# StandaloneLeakDetector.net
KiCad netlist of a schematic drawn in Altium Designer
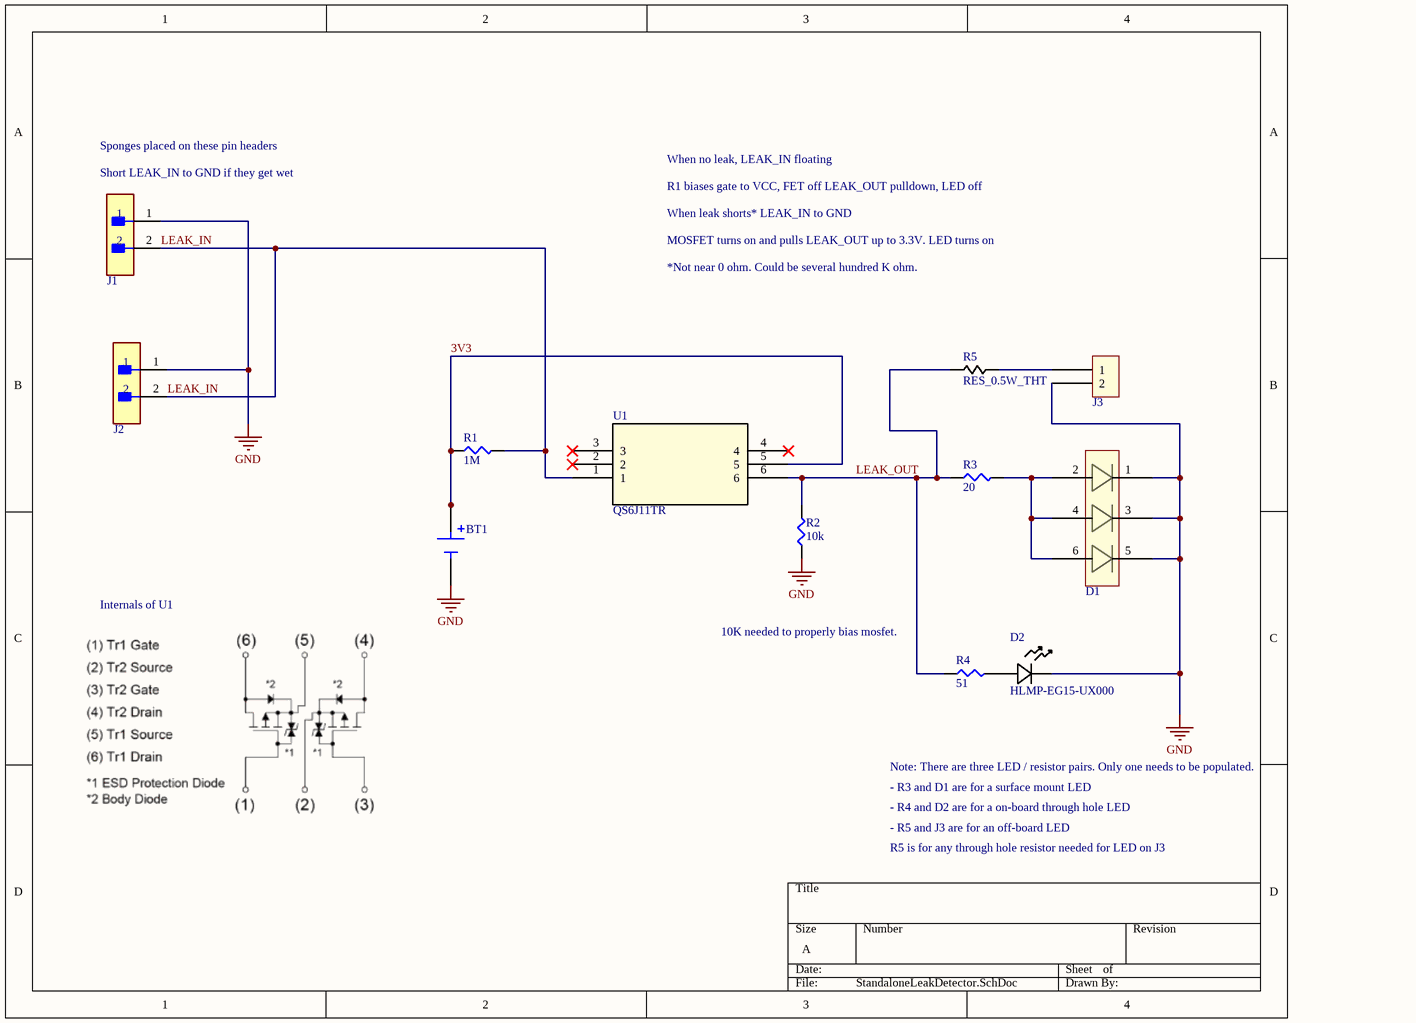
[diagram p0: StandaloneLeakDetector.SchDoc]

(export (version "E")
  (design (tool "Eeschema 10.0.6"))
  (components
    (comp (ref "BT1")
      (value "BAT-HLD-005-THM")
      (footprint "BAT_BAT-HLD-005-THM")
      (description "Battery Retainer Coin, 20.0mm 1 Cell PC Pin")
      (fields (field (name "MF") "Linx Technologies Inc."))
      (libsource (lib "URC_Lib") (part "BAT-HLD-005-THM"))
    )
    (comp (ref "D1") (value "SMTL6-RC") (footprint "SMTL6-RC") (libsource (lib "URC_Lib") (part "SMTL6-RC")))
    (comp (ref "D2")
      (value "HLMP-EG15-UX000")
      (footprint "LED_AVAGO_HLMP_XX15_AVA")
      (description "No Description Available")
      (fields (field (name "COPYRIGHT") "Copyright (C) 2022 Ultra Librarian. All rights reserved."))
      (libsource (lib "URC_Lib") (part "HLMP-EG15-UX000"))
    )
    (comp (ref "J1")
      (value "TSW-102-07-L-S")
      (footprint "FP-TSW-102-07-L-S-MFG")
      (description "CONN HEADER VERT 2POS 2.54MM")
      (libsource (lib "Altium Content Vault") (part "3bc925449376181038e59eaffc5286c"))
    )
    (comp (ref "J2")
      (value "TSW-102-07-L-S")
      (footprint "FP-TSW-102-07-L-S-MFG")
      (description "CONN HEADER VERT 2POS 2.54MM")
      (libsource (lib "Altium Content Vault") (part "3bc925449376181038e59eaffc5286c"))
    )
    (comp (ref "J3")
      (value "Header")
      (footprint "1x2 Header")
      (description "CONN HEADER VERT 2POS 2.54MM")
      (libsource (lib "URC_Lib") (part "1x2 Header"))
    )
    (comp (ref "R1")
      (value "1M")
      (footprint "SMD-0805-RES")
      (description "RES SMD 1M OHM 1% 1/8W 0805")
      (fields
        (field (name "PART NUMBER") "ERJ-6ENF1004V")
        (field (name "DIGI-KEY PART NUMBER") "P1.00MCCT-ND")
      )
      (libsource (lib "Panasonic_resistor_0805") (part "ERJ-6ENF1004V"))
    )
    (comp (ref "R2")
      (value "10k")
      (footprint "SMD-0805-RES")
      (description "RES SMD 10K OHM 1% 1/8W 0805")
      (fields
        (field (name "PART NUMBER") "ERJ-6ENF1002V")
        (field (name "DIGI-KEY PART NUMBER") "P10.0KCCT-ND")
      )
      (libsource (lib "Panasonic_resistor_0805") (part "ERJ-6ENF1002V"))
    )
    (comp (ref "R3")
      (value "20")
      (footprint "SMD-0805-RES")
      (description "RES SMD 20 OHM 1% 1/8W 0805")
      (fields
        (field (name "PART NUMBER") "ERJ-6ENF20R0V")
        (field (name "DIGI-KEY PART NUMBER") "P20.0CCT-ND")
      )
      (libsource (lib "Panasonic_resistor_0805") (part "ERJ-6ENF20R0V"))
    )
    (comp (ref "R4")
      (value "51")
      (footprint "SMD-0805-RES")
      (description "RES SMD 51 OHM 5% 1/8W 0805")
      (fields (field (name "PART NUMBER") "ERJ-6GEYJ510V") (field (name "DIGI-KEY PART NUMBER") "P51ACT-ND"))
      (libsource (lib "Panasonic_resistor_0805") (part "ERJ-6GEYJ510V"))
    )
    (comp (ref "R5")
      (value "RES_0.5W_THT")
      (footprint "RES_0.5W_THT")
      (description "Generic 0.5W through hole resistor")
      (libsource (lib "URC_Lib") (part "RES_0.5W_THT"))
    )
    (comp (ref "U1")
      (value "QS6J11TR")
      (footprint "TRANS_QS6_ROM")
      (description "No Description Available")
      (fields (field (name "COPYRIGHT") "Copyright (C) 2022 Ultra Librarian. All rights reserved."))
      (libsource (lib "URC_Lib") (part "QS6J11TR"))
    )
  )
  (nets
    (net (code "1") (name "/3V3") (class "Default")
      (node (ref "BT1") (pin "P1") (pinfunction "POS_P1") (pintype "passive"))
      (node (ref "BT1") (pin "P2") (pinfunction "POS_P2") (pintype "passive"))
      (node (ref "R1") (pin "1") (pinfunction "1_1") (pintype "passive"))
      (node (ref "U1") (pin "5") (pinfunction "5_5") (pintype "passive"))
    )
    (net (code "2") (name "/LEAK_IN") (class "Default")
      (node (ref "J1") (pin "2") (pinfunction "2_2") (pintype "passive"))
      (node (ref "J2") (pin "2") (pinfunction "2_2") (pintype "passive"))
      (node (ref "R1") (pin "2") (pinfunction "2_2") (pintype "passive"))
      (node (ref "U1") (pin "1") (pinfunction "1_1") (pintype "passive"))
    )
    (net (code "3") (name "/LEAK_OUT") (class "Default")
      (node (ref "R2") (pin "2") (pinfunction "2_2") (pintype "passive"))
      (node (ref "R3") (pin "1") (pinfunction "1_1") (pintype "passive"))
      (node (ref "R4") (pin "1") (pinfunction "1_1") (pintype "passive"))
      (node (ref "R5") (pin "1") (pinfunction "1_1") (pintype "passive"))
      (node (ref "U1") (pin "6") (pinfunction "6_6") (pintype "passive"))
    )
    (net (code "4") (name "GND") (class "Default")
      (node (ref "BT1") (pin "N") (pinfunction "NEG_N") (pintype "passive"))
      (node (ref "D1") (pin "1") (pinfunction "1_1") (pintype "passive"))
      (node (ref "D1") (pin "3") (pinfunction "3_3") (pintype "passive"))
      (node (ref "D1") (pin "5") (pinfunction "5_5") (pintype "passive"))
      (node (ref "D2") (pin "1") (pinfunction "1_1") (pintype "passive"))
      (node (ref "J1") (pin "1") (pinfunction "1_1") (pintype "passive"))
      (node (ref "J2") (pin "1") (pinfunction "1_1") (pintype "passive"))
      (node (ref "J3") (pin "2") (pinfunction "2_2") (pintype "passive"))
      (node (ref "R2") (pin "1") (pinfunction "1_1") (pintype "passive"))
    )
    (net (code "5") (name "Net-(D1-Pad2)") (class "Default")
      (node (ref "D1") (pin "2") (pinfunction "2_2") (pintype "passive"))
      (node (ref "D1") (pin "4") (pinfunction "4_4") (pintype "passive"))
      (node (ref "D1") (pin "6") (pinfunction "6_6") (pintype "passive"))
      (node (ref "R3") (pin "2") (pinfunction "2_2") (pintype "passive"))
    )
    (net (code "6") (name "Net-(D2-Pad2)") (class "Default")
      (node (ref "D2") (pin "2") (pinfunction "2_2") (pintype "passive"))
      (node (ref "R4") (pin "2") (pinfunction "2_2") (pintype "passive"))
    )
    (net (code "7") (name "Net-(J3-Pad1)") (class "Default")
      (node (ref "J3") (pin "1") (pinfunction "1_1") (pintype "passive"))
      (node (ref "R5") (pin "2") (pinfunction "2_2") (pintype "passive"))
    )
    (net (code "8") (name "unconnected-(U1-Pad2)") (class "Default")
      (node (ref "U1") (pin "2") (pinfunction "2_2") (pintype "passive+no_connect"))
    )
    (net (code "9") (name "unconnected-(U1-Pad3)") (class "Default")
      (node (ref "U1") (pin "3") (pinfunction "3_3") (pintype "passive+no_connect"))
    )
    (net (code "10") (name "unconnected-(U1-Pad4)") (class "Default")
      (node (ref "U1") (pin "4") (pinfunction "4_4") (pintype "passive+no_connect"))
    )
  )
)
